# pepitaBadge.net
KiCad netlist of a schematic drawn in EAGLE
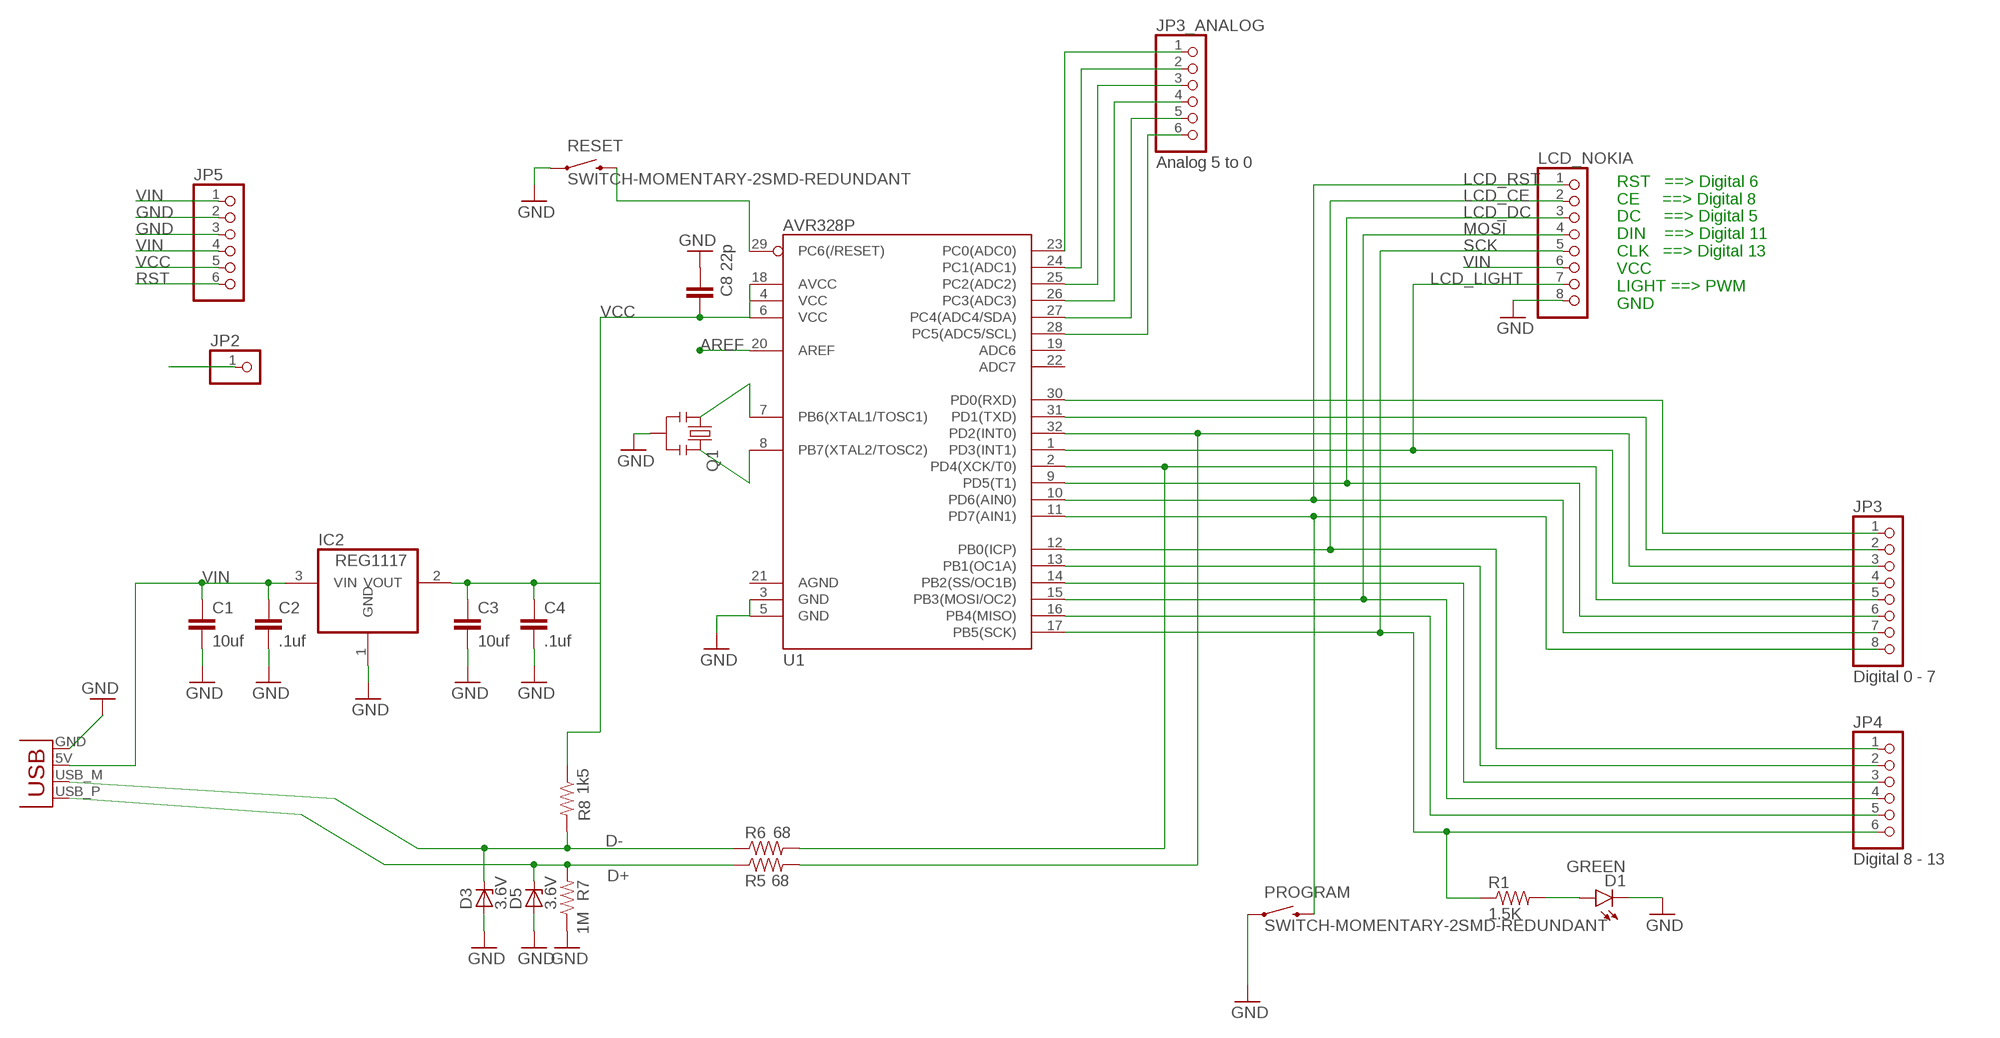
[diagram p0: schematic, sheet 1]

(export (version "E")
  (design (tool "Eeschema 10.0.6"))
  (components
    (comp (ref "C1")
      (value "10uf")
      (footprint "eagle-import:0805")
      (libsource (lib "eagle-import") (part "22UF-6.3V-20%(0805)"))
    )
    (comp (ref "C2")
      (value ".1uf")
      (footprint "eagle-import:0603-CAP")
      (libsource (lib "eagle-import") (part "CAP0603-CAP"))
    )
    (comp (ref "C3")
      (value "10uf")
      (footprint "eagle-import:0805")
      (libsource (lib "eagle-import") (part "22UF-6.3V-20%(0805)"))
    )
    (comp (ref "C4")
      (value ".1uf")
      (footprint "eagle-import:0603-CAP")
      (libsource (lib "eagle-import") (part "CAP0603-CAP"))
    )
    (comp (ref "C8")
      (value "22p")
      (footprint "eagle-import:0603-CAP")
      (libsource (lib "eagle-import") (part "CAP0603-CAP"))
    )
    (comp (ref "D1")
      (value "GREEN")
      (footprint "eagle-import:LED-0603")
      (libsource (lib "eagle-import") (part "LED-GREEN0603"))
    )
    (comp (ref "D3")
      (value "3.6V")
      (footprint "eagle-import:1206")
      (libsource (lib "eagle-import") (part "ZENER-DIODE"))
    )
    (comp (ref "D5")
      (value "3.6V")
      (footprint "eagle-import:1206")
      (libsource (lib "eagle-import") (part "ZENER-DIODE"))
    )
    (comp (ref "IC2")
      (value "REG1117")
      (footprint "eagle-import:SOT223")
      (libsource (lib "eagle-import") (part "REG1117"))
    )
    (comp (ref "JP1")
      (value "USBPCB")
      (footprint "eagle-import:USB-A-PCB")
      (libsource (lib "eagle-import") (part "USBPCB"))
    )
    (comp (ref "JP2")
      (value "PINHD-1X1")
      (footprint "eagle-import:1X01")
      (libsource (lib "eagle-import") (part "PINHD-1X1"))
    )
    (comp (ref "JP3")
      (value "Digital 0 - 7")
      (footprint "eagle-import:1X08")
      (libsource (lib "eagle-import") (part "PINHD-1X8"))
    )
    (comp (ref "JP3_ANALOG")
      (value "Analog 5 to 0")
      (footprint "eagle-import:1X06")
      (libsource (lib "eagle-import") (part "PINHD-1X6"))
    )
    (comp (ref "JP4")
      (value "Digital 8 - 13")
      (footprint "eagle-import:1X06")
      (libsource (lib "eagle-import") (part "PINHD-1X6"))
    )
    (comp (ref "JP5")
      (value "PINHD-1X6")
      (footprint "eagle-import:1X06")
      (libsource (lib "eagle-import") (part "PINHD-1X6"))
    )
    (comp (ref "LCD_NOKIA")
      (value "PINHD-1X8")
      (footprint "eagle-import:1X08")
      (libsource (lib "eagle-import") (part "PINHD-1X8"))
    )
    (comp (ref "PROGRAM")
      (value "SWITCH-MOMENTARY-2SMD-REDUNDANT")
      (footprint "eagle-import:TACTILE-SWITCH-SMD")
      (libsource (lib "eagle-import") (part "SWITCH-MOMENTARY-2SMD-REDUNDANT"))
    )
    (comp (ref "Q1")
      (value "RESONATOR16MHZ")
      (footprint "eagle-import:RESONATOR-SMD")
      (libsource (lib "eagle-import") (part "RESONATOR16MHZ"))
    )
    (comp (ref "R1")
      (value "1.5K")
      (footprint "eagle-import:0603-RES")
      (libsource (lib "eagle-import") (part "RESISTOR0603-RES"))
    )
    (comp (ref "R5")
      (value "68")
      (footprint "eagle-import:0603-RES")
      (libsource (lib "eagle-import") (part "RESISTOR0603-RES"))
    )
    (comp (ref "R6")
      (value "68")
      (footprint "eagle-import:0603-RES")
      (libsource (lib "eagle-import") (part "RESISTOR0603-RES"))
    )
    (comp (ref "R7")
      (value "1M")
      (footprint "eagle-import:0603-RES")
      (libsource (lib "eagle-import") (part "RESISTOR0603-RES"))
    )
    (comp (ref "R8")
      (value "1k5")
      (footprint "eagle-import:0603-RES")
      (libsource (lib "eagle-import") (part "RESISTOR0603-RES"))
    )
    (comp (ref "RESET")
      (value "SWITCH-MOMENTARY-2SMD-REDUNDANT")
      (footprint "eagle-import:TACTILE-SWITCH-SMD")
      (libsource (lib "eagle-import") (part "SWITCH-MOMENTARY-2SMD-REDUNDANT"))
    )
    (comp (ref "U1")
      (value "AVR328P")
      (footprint "eagle-import:TQFP32-08")
      (libsource (lib "eagle-import") (part "ATMEGA328_SMT"))
    )
  )
  (nets
    (net (code "1") (name "/AREF") (class "Default")
      (node (ref "JP2") (pin "1") (pinfunction "1_1") (pintype "passive"))
      (node (ref "U1") (pin "20") (pinfunction "AREF_20") (pintype "bidirectional"))
    )
    (net (code "2") (name "/D+") (class "Default")
      (node (ref "D5") (pin "2") (pinfunction "C_2") (pintype "passive"))
      (node (ref "JP1") (pin "USB_P") (pinfunction "D+_USB_P") (pintype "bidirectional"))
      (node (ref "R5") (pin "1") (pinfunction "1_1") (pintype "passive"))
      (node (ref "R7") (pin "2") (pinfunction "2_2") (pintype "passive"))
    )
    (net (code "3") (name "/D-") (class "Default")
      (node (ref "D3") (pin "2") (pinfunction "C_2") (pintype "passive"))
      (node (ref "JP1") (pin "USB_M") (pinfunction "D-_USB_M") (pintype "bidirectional"))
      (node (ref "R6") (pin "1") (pinfunction "1_1") (pintype "passive"))
      (node (ref "R8") (pin "2") (pinfunction "2_2") (pintype "passive"))
    )
    (net (code "4") (name "/LCD_CE") (class "Default")
      (node (ref "JP4") (pin "1") (pinfunction "1_1") (pintype "passive"))
      (node (ref "LCD_NOKIA") (pin "2") (pinfunction "2_2") (pintype "passive"))
      (node (ref "U1") (pin "12") (pinfunction "PB0(ICP)_12") (pintype "bidirectional"))
    )
    (net (code "5") (name "/LCD_DC") (class "Default")
      (node (ref "JP3") (pin "6") (pinfunction "6_6") (pintype "passive"))
      (node (ref "LCD_NOKIA") (pin "3") (pinfunction "3_3") (pintype "passive"))
      (node (ref "U1") (pin "9") (pinfunction "PD5(T1)_9") (pintype "bidirectional"))
    )
    (net (code "6") (name "/LCD_LIGHT") (class "Default")
      (node (ref "JP3") (pin "4") (pinfunction "4_4") (pintype "passive"))
      (node (ref "LCD_NOKIA") (pin "7") (pinfunction "7_7") (pintype "passive"))
      (node (ref "U1") (pin "1") (pinfunction "PD3(INT1)_1") (pintype "bidirectional"))
    )
    (net (code "7") (name "/LCD_RST") (class "Default")
      (node (ref "JP3") (pin "7") (pinfunction "7_7") (pintype "passive"))
      (node (ref "LCD_NOKIA") (pin "1") (pinfunction "1_1") (pintype "passive"))
      (node (ref "U1") (pin "10") (pinfunction "PD6(AIN0)_10") (pintype "bidirectional"))
    )
    (net (code "8") (name "/MOSI") (class "Default")
      (node (ref "JP4") (pin "4") (pinfunction "4_4") (pintype "passive"))
      (node (ref "LCD_NOKIA") (pin "4") (pinfunction "4_4") (pintype "passive"))
      (node (ref "U1") (pin "15") (pinfunction "PB3(MOSI/OC2)_15") (pintype "bidirectional"))
    )
    (net (code "9") (name "/RST") (class "Default")
      (node (ref "JP5") (pin "6") (pinfunction "6_6") (pintype "passive"))
      (node (ref "RESET") (pin "3") (pinfunction "2_3") (pintype "passive"))
      (node (ref "RESET") (pin "4") (pinfunction "2_4") (pintype "passive"))
      (node (ref "U1") (pin "29") (pinfunction "PC6(/RESET)_29") (pintype "bidirectional"))
    )
    (net (code "10") (name "/SCK") (class "Default")
      (node (ref "JP4") (pin "6") (pinfunction "6_6") (pintype "passive"))
      (node (ref "LCD_NOKIA") (pin "5") (pinfunction "5_5") (pintype "passive"))
      (node (ref "R1") (pin "1") (pinfunction "1_1") (pintype "passive"))
      (node (ref "U1") (pin "17") (pinfunction "PB5(SCK)_17") (pintype "bidirectional"))
    )
    (net (code "11") (name "/VCC") (class "Default")
      (node (ref "C3") (pin "1") (pinfunction "1_1") (pintype "passive"))
      (node (ref "C4") (pin "1") (pinfunction "1_1") (pintype "passive"))
      (node (ref "C8") (pin "1") (pinfunction "1_1") (pintype "passive"))
      (node (ref "IC2") (pin "2") (pinfunction "VOUT_2") (pintype "output"))
      (node (ref "JP5") (pin "5") (pinfunction "5_5") (pintype "passive"))
      (node (ref "R8") (pin "1") (pinfunction "1_1") (pintype "passive"))
      (node (ref "U1") (pin "18") (pinfunction "AVCC_18") (pintype "bidirectional"))
      (node (ref "U1") (pin "4") (pinfunction "VCC_4") (pintype "bidirectional"))
      (node (ref "U1") (pin "6") (pinfunction "VCC_6") (pintype "bidirectional"))
    )
    (net (code "12") (name "/VIN") (class "Default")
      (node (ref "C1") (pin "1") (pinfunction "1_1") (pintype "passive"))
      (node (ref "C2") (pin "1") (pinfunction "1_1") (pintype "passive"))
      (node (ref "IC2") (pin "3") (pinfunction "VIN_3") (pintype "input"))
      (node (ref "JP1") (pin "5V") (pinfunction "VBUS_5V") (pintype "bidirectional"))
      (node (ref "JP5") (pin "1") (pinfunction "1_1") (pintype "passive"))
      (node (ref "JP5") (pin "4") (pinfunction "4_4") (pintype "passive"))
      (node (ref "LCD_NOKIA") (pin "6") (pinfunction "6_6") (pintype "passive"))
    )
    (net (code "13") (name "GND") (class "Default")
      (node (ref "C1") (pin "2") (pinfunction "2_2") (pintype "passive"))
      (node (ref "C2") (pin "2") (pinfunction "2_2") (pintype "passive"))
      (node (ref "C3") (pin "2") (pinfunction "2_2") (pintype "passive"))
      (node (ref "C4") (pin "2") (pinfunction "2_2") (pintype "passive"))
      (node (ref "C8") (pin "2") (pinfunction "2_2") (pintype "passive"))
      (node (ref "D1") (pin "C") (pinfunction "C_C") (pintype "passive"))
      (node (ref "D3") (pin "1") (pinfunction "A_1") (pintype "passive"))
      (node (ref "D5") (pin "1") (pinfunction "A_1") (pintype "passive"))
      (node (ref "IC2") (pin "1") (pinfunction "GND_1") (pintype "power_in"))
      (node (ref "JP1") (pin "GND") (pinfunction "GND_GND") (pintype "bidirectional"))
      (node (ref "JP5") (pin "2") (pinfunction "2_2") (pintype "passive"))
      (node (ref "JP5") (pin "3") (pinfunction "3_3") (pintype "passive"))
      (node (ref "LCD_NOKIA") (pin "8") (pinfunction "8_8") (pintype "passive"))
      (node (ref "PROGRAM") (pin "1") (pinfunction "1_1") (pintype "passive"))
      (node (ref "PROGRAM") (pin "2") (pinfunction "1_2") (pintype "passive"))
      (node (ref "Q1") (pin "2") (pinfunction "2_2") (pintype "passive"))
      (node (ref "R7") (pin "1") (pinfunction "1_1") (pintype "passive"))
      (node (ref "RESET") (pin "1") (pinfunction "1_1") (pintype "passive"))
      (node (ref "RESET") (pin "2") (pinfunction "1_2") (pintype "passive"))
      (node (ref "U1") (pin "3") (pinfunction "GND_3") (pintype "bidirectional"))
      (node (ref "U1") (pin "5") (pinfunction "GND_5") (pintype "bidirectional"))
    )
    (net (code "14") (name "Net-(D1-PadA)") (class "Default")
      (node (ref "D1") (pin "A") (pinfunction "A_A") (pintype "passive"))
      (node (ref "R1") (pin "2") (pinfunction "2_2") (pintype "passive"))
    )
    (net (code "15") (name "Net-(U1-PB1(OC1A))") (class "Default")
      (node (ref "JP4") (pin "2") (pinfunction "2_2") (pintype "passive"))
      (node (ref "U1") (pin "13") (pinfunction "PB1(OC1A)_13") (pintype "bidirectional"))
    )
    (net (code "16") (name "Net-(U1-PB2(SS{slash}OC1B))") (class "Default")
      (node (ref "JP4") (pin "3") (pinfunction "3_3") (pintype "passive"))
      (node (ref "U1") (pin "14") (pinfunction "PB2(SS/OC1B)_14") (pintype "bidirectional"))
    )
    (net (code "17") (name "Net-(U1-PB4(MISO))") (class "Default")
      (node (ref "JP4") (pin "5") (pinfunction "5_5") (pintype "passive"))
      (node (ref "U1") (pin "16") (pinfunction "PB4(MISO)_16") (pintype "bidirectional"))
    )
    (net (code "18") (name "Net-(U1-PB6(XTAL1{slash}TOSC1))") (class "Default")
      (node (ref "Q1") (pin "1") (pinfunction "1_1") (pintype "passive"))
      (node (ref "U1") (pin "7") (pinfunction "PB6(XTAL1/TOSC1)_7") (pintype "bidirectional"))
    )
    (net (code "19") (name "Net-(U1-PB7(XTAL2{slash}TOSC2))") (class "Default")
      (node (ref "Q1") (pin "3") (pinfunction "3_3") (pintype "passive"))
      (node (ref "U1") (pin "8") (pinfunction "PB7(XTAL2/TOSC2)_8") (pintype "bidirectional"))
    )
    (net (code "20") (name "Net-(U1-PC0(ADC0))") (class "Default")
      (node (ref "JP3_ANALOG") (pin "1") (pinfunction "1_1") (pintype "passive"))
      (node (ref "U1") (pin "23") (pinfunction "PC0(ADC0)_23") (pintype "bidirectional"))
    )
    (net (code "21") (name "Net-(U1-PC1(ADC1))") (class "Default")
      (node (ref "JP3_ANALOG") (pin "2") (pinfunction "2_2") (pintype "passive"))
      (node (ref "U1") (pin "24") (pinfunction "PC1(ADC1)_24") (pintype "bidirectional"))
    )
    (net (code "22") (name "Net-(U1-PC2(ADC2))") (class "Default")
      (node (ref "JP3_ANALOG") (pin "3") (pinfunction "3_3") (pintype "passive"))
      (node (ref "U1") (pin "25") (pinfunction "PC2(ADC2)_25") (pintype "bidirectional"))
    )
    (net (code "23") (name "Net-(U1-PC3(ADC3))") (class "Default")
      (node (ref "JP3_ANALOG") (pin "4") (pinfunction "4_4") (pintype "passive"))
      (node (ref "U1") (pin "26") (pinfunction "PC3(ADC3)_26") (pintype "bidirectional"))
    )
    (net (code "24") (name "Net-(U1-PC4(ADC4{slash}SDA))") (class "Default")
      (node (ref "JP3_ANALOG") (pin "5") (pinfunction "5_5") (pintype "passive"))
      (node (ref "U1") (pin "27") (pinfunction "PC4(ADC4/SDA)_27") (pintype "bidirectional"))
    )
    (net (code "25") (name "Net-(U1-PC5(ADC5{slash}SCL))") (class "Default")
      (node (ref "JP3_ANALOG") (pin "6") (pinfunction "6_6") (pintype "passive"))
      (node (ref "U1") (pin "28") (pinfunction "PC5(ADC5/SCL)_28") (pintype "bidirectional"))
    )
    (net (code "26") (name "Net-(U1-PD0(RXD))") (class "Default")
      (node (ref "JP3") (pin "1") (pinfunction "1_1") (pintype "passive"))
      (node (ref "U1") (pin "30") (pinfunction "PD0(RXD)_30") (pintype "bidirectional"))
    )
    (net (code "27") (name "Net-(U1-PD1(TXD))") (class "Default")
      (node (ref "JP3") (pin "2") (pinfunction "2_2") (pintype "passive"))
      (node (ref "U1") (pin "31") (pinfunction "PD1(TXD)_31") (pintype "bidirectional"))
    )
    (net (code "28") (name "Net-(U1-PD2(INT0))") (class "Default")
      (node (ref "JP3") (pin "3") (pinfunction "3_3") (pintype "passive"))
      (node (ref "R5") (pin "2") (pinfunction "2_2") (pintype "passive"))
      (node (ref "U1") (pin "32") (pinfunction "PD2(INT0)_32") (pintype "bidirectional"))
    )
    (net (code "29") (name "Net-(U1-PD4(XCK{slash}T0))") (class "Default")
      (node (ref "JP3") (pin "5") (pinfunction "5_5") (pintype "passive"))
      (node (ref "R6") (pin "2") (pinfunction "2_2") (pintype "passive"))
      (node (ref "U1") (pin "2") (pinfunction "PD4(XCK/T0)_2") (pintype "bidirectional"))
    )
    (net (code "30") (name "Net-(U1-PD7(AIN1))") (class "Default")
      (node (ref "JP3") (pin "8") (pinfunction "8_8") (pintype "passive"))
      (node (ref "PROGRAM") (pin "3") (pinfunction "2_3") (pintype "passive"))
      (node (ref "PROGRAM") (pin "4") (pinfunction "2_4") (pintype "passive"))
      (node (ref "U1") (pin "11") (pinfunction "PD7(AIN1)_11") (pintype "bidirectional"))
    )
    (net (code "31") (name "unconnected-(U1-ADC6-Pad19)") (class "Default")
      (node (ref "U1") (pin "19") (pinfunction "ADC6_19") (pintype "bidirectional"))
    )
    (net (code "32") (name "unconnected-(U1-ADC7-Pad22)") (class "Default")
      (node (ref "U1") (pin "22") (pinfunction "ADC7_22") (pintype "bidirectional"))
    )
    (net (code "33") (name "unconnected-(U1-AGND-Pad21)") (class "Default")
      (node (ref "U1") (pin "21") (pinfunction "AGND_21") (pintype "bidirectional"))
    )
  )
)
